# Wire_Puzzle.net
KiCad netlist of a schematic drawn in EAGLE
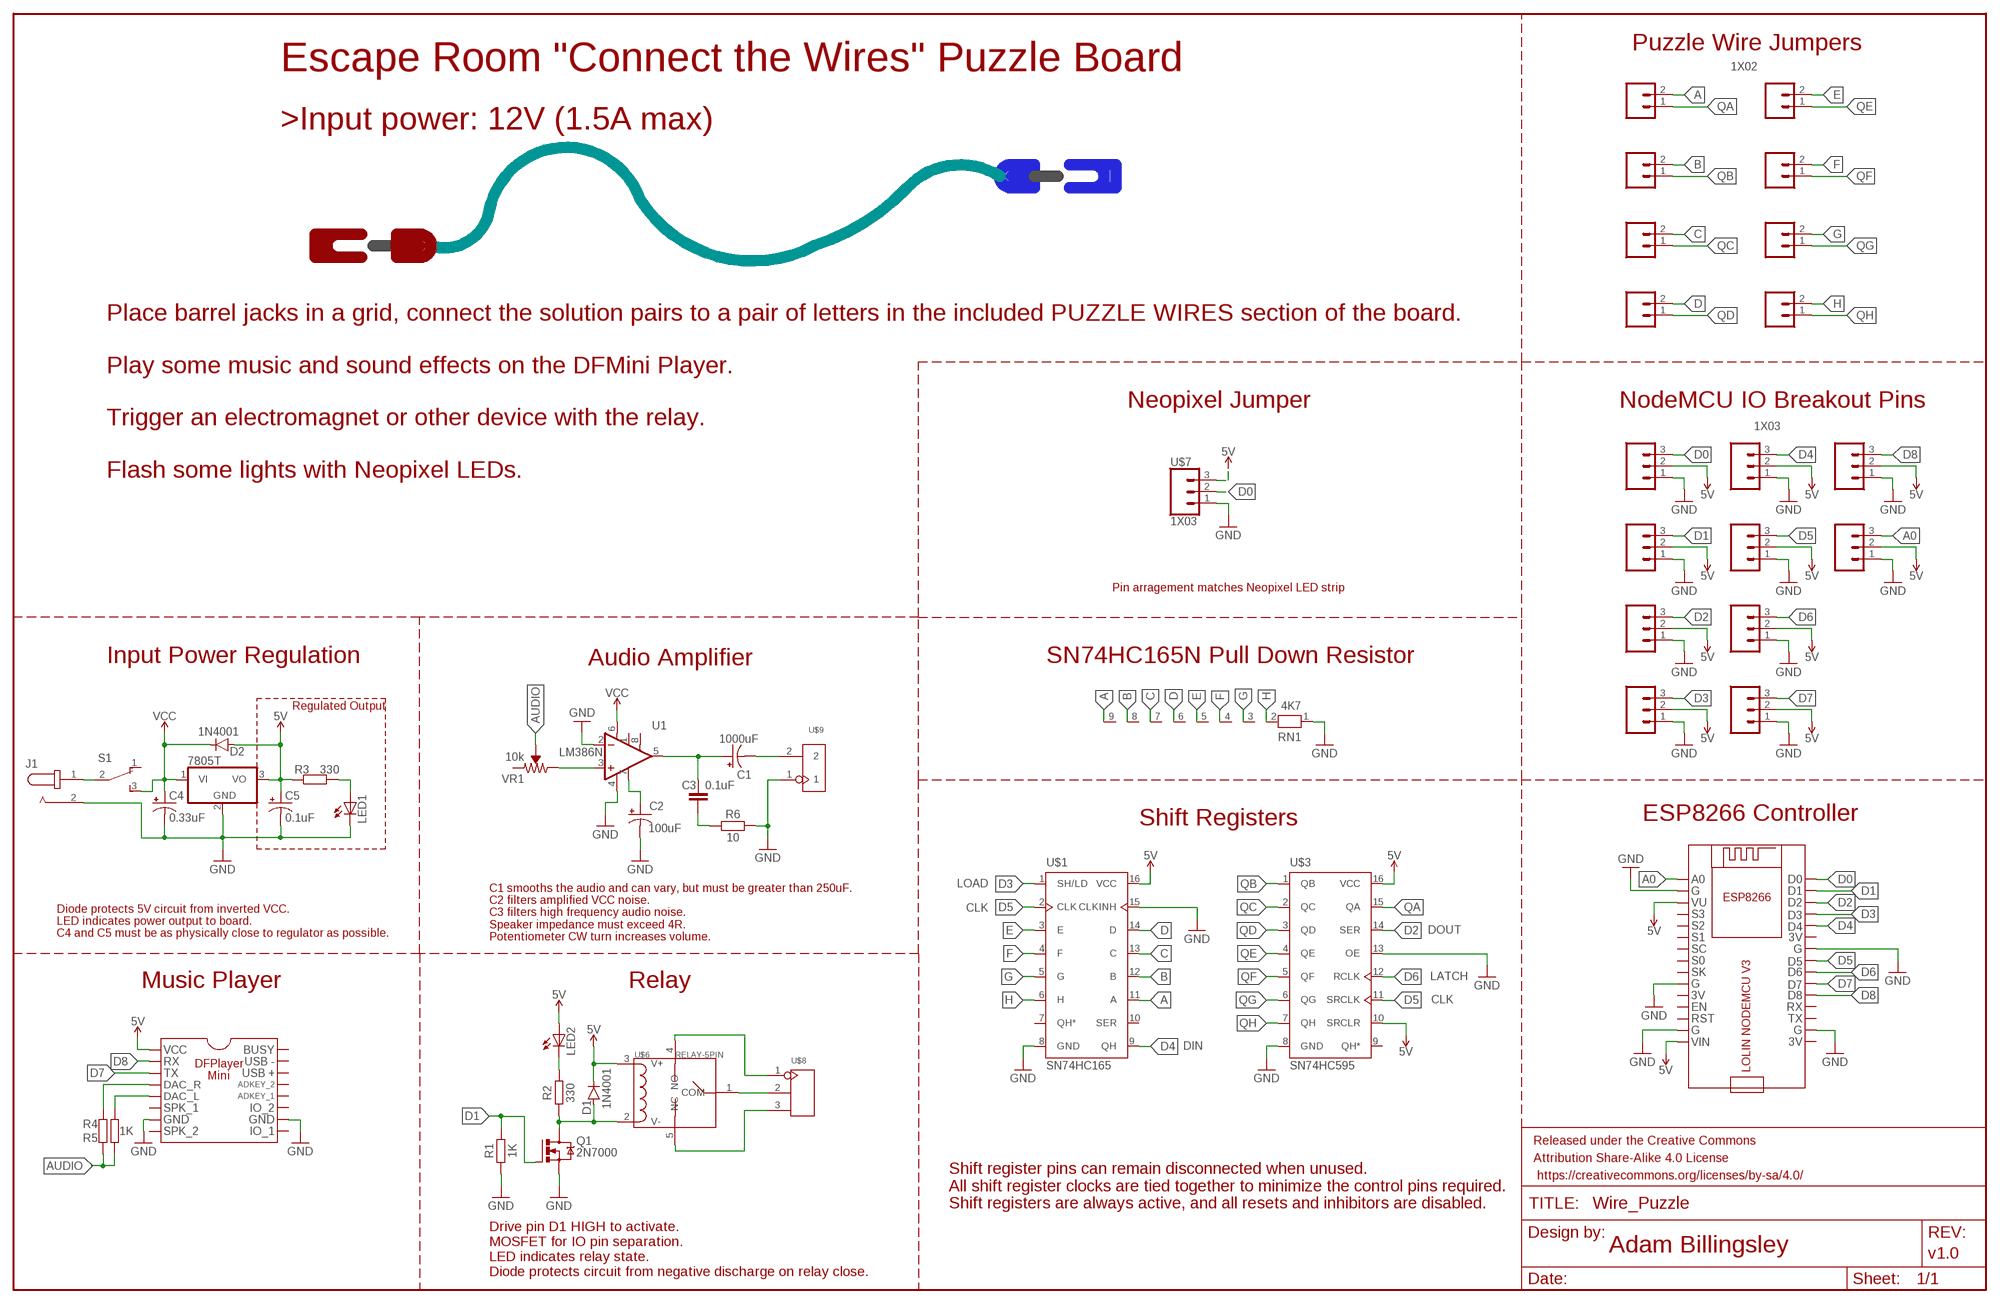
[diagram p0: schematic, sheet 1]

(export (version "E")
  (design (tool "Eeschema 10.0.6"))
  (components
    (comp (ref "C1")
      (value "1000uF")
      (footprint "eagle-import:E5-10,5")
      (libsource (lib "eagle-import") (part "CPOL-USE5-10.5"))
    )
    (comp (ref "C2")
      (value "100uF")
      (footprint "eagle-import:E5-10,5")
      (libsource (lib "eagle-import") (part "CPOL-USE5-10.5"))
    )
    (comp (ref "C3")
      (value "0.1uF")
      (footprint "eagle-import:C2.5-2")
      (libsource (lib "eagle-import") (part "C2.5/2"))
    )
    (comp (ref "C4")
      (value "0.33uF")
      (footprint "eagle-import:E2-5")
      (libsource (lib "eagle-import") (part "rcl_334_CPOL-USE2-5"))
    )
    (comp (ref "C5")
      (value "0.1uF")
      (footprint "eagle-import:E2-5")
      (libsource (lib "eagle-import") (part "rcl_334_CPOL-USE2-5"))
    )
    (comp (ref "D1")
      (value "1N4001")
      (footprint "eagle-import:DO-41")
      (fields
        (field (name "DIGIKEY_PART_NUMBER") "1N4004MSCT-ND")
        (field (name "MANUFACTURER") "Micro Commercial Co")
        (field (name "MPN") "1N4004")
        (field (name "CREATED_BY") "PCBLayout.com")
      )
      (libsource (lib "eagle-import") (part "1N4004"))
    )
    (comp (ref "D2")
      (value "1N4001")
      (footprint "eagle-import:DO-41")
      (fields
        (field (name "DIGIKEY_PART_NUMBER") "1N4004MSCT-ND")
        (field (name "MANUFACTURER") "Micro Commercial Co")
        (field (name "MPN") "1N4004")
        (field (name "CREATED_BY") "PCBLayout.com")
      )
      (libsource (lib "eagle-import") (part "1N4004"))
    )
    (comp (ref "FRAME1")
      (value "FRAME-LEDGER")
      (footprint "eagle-import:CREATIVE_COMMONS")
      (libsource (lib "eagle-import") (part "FRAME-LEDGER"))
    )
    (comp (ref "IC1")
      (value "7805T")
      (footprint "eagle-import:TO220H")
      (libsource (lib "eagle-import") (part "78T05"))
    )
    (comp (ref "J1")
      (value "POWER_JACK_PJ-037A")
      (footprint "eagle-import:CUI_PJ-037A")
      (fields (field (name "MANUFACTURER") "CUI INC"))
      (libsource (lib "eagle-import") (part "POWER_JACK_PJ-037A"))
    )
    (comp (ref "LED1")
      (value "LED5MM")
      (footprint "eagle-import:LED5MM")
      (libsource (lib "eagle-import") (part "LED5MM"))
    )
    (comp (ref "LED2")
      (value "LED5MM")
      (footprint "eagle-import:LED5MM")
      (libsource (lib "eagle-import") (part "LED5MM"))
    )
    (comp (ref "Q1")
      (value "2N7000")
      (footprint "eagle-import:TO92")
      (libsource (lib "eagle-import") (part "NMOSFET_TO92_"))
    )
    (comp (ref "R1")
      (value "1K")
      (footprint "eagle-import:RESAD724W46L381D178B")
      (libsource (lib "eagle-import") (part "RAXIAL-7.2MM-PITCH_"))
    )
    (comp (ref "R2")
      (value "330")
      (footprint "eagle-import:RESAD724W46L381D178B")
      (libsource (lib "eagle-import") (part "RAXIAL-7.2MM-PITCH_"))
    )
    (comp (ref "R3")
      (value "330")
      (footprint "eagle-import:RESAD724W46L381D178B")
      (libsource (lib "eagle-import") (part "RAXIAL-7.2MM-PITCH_"))
    )
    (comp (ref "R4")
      (value "1K")
      (footprint "eagle-import:RESAD724W46L381D178B")
      (libsource (lib "eagle-import") (part "RAXIAL-7.2MM-PITCH_"))
    )
    (comp (ref "R5")
      (value "1K")
      (footprint "eagle-import:RESAD724W46L381D178B")
      (libsource (lib "eagle-import") (part "RAXIAL-7.2MM-PITCH_"))
    )
    (comp (ref "R6")
      (value "10")
      (footprint "eagle-import:RESAD724W46L381D178B")
      (libsource (lib "eagle-import") (part "RAXIAL-7.2MM-PITCH_"))
    )
    (comp (ref "RN1")
      (value "4K7")
      (footprint "eagle-import:RN-9")
      (libsource (lib "eagle-import") (part "RN08"))
    )
    (comp (ref "S1")
      (value "SWITCH_SLIDING_SSP1S1")
      (footprint "eagle-import:SWITCH_SLIDING_SSP1S1")
      (libsource (lib "eagle-import") (part "SWITCH_SLIDING_SSP1S1"))
    )
    (comp (ref "U$1")
      (value "SN74HC165")
      (footprint "eagle-import:DIL16")
      (libsource (lib "eagle-import") (part "SN74HC165"))
    )
    (comp (ref "U$3")
      (value "SN74HC595")
      (footprint "eagle-import:DIL16")
      (libsource (lib "eagle-import") (part "SN74HC595"))
    )
    (comp (ref "U$4")
      (value "LOLIN_NODEMCU")
      (footprint "eagle-import:LOLIN_NODEMCU")
      (libsource (lib "eagle-import") (part "LOLIN_NODEMCU"))
    )
    (comp (ref "U$5")
      (value "DFPLAYER_MINI")
      (footprint "eagle-import:DFMINI")
      (libsource (lib "eagle-import") (part "DFPLAYER_MINI"))
    )
    (comp (ref "U$6")
      (value "RELAY-5PIN")
      (footprint "eagle-import:RELAY-19.0X15.0X15.0MM")
      (libsource (lib "eagle-import") (part "RELAY-5PIN"))
    )
    (comp (ref "U$7")
      (value "1X03")
      (footprint "eagle-import:1X03")
      (libsource (lib "eagle-import") (part "1X03"))
    )
    (comp (ref "U$8")
      (value "TERMINAL_BLOCK_3P")
      (footprint "eagle-import:H3-5.0-15.5X8.0MM")
      (libsource (lib "eagle-import") (part "TERMINAL_BLOCK_3P"))
    )
    (comp (ref "U$9")
      (value "TERMINAL_BLOCK_2P")
      (footprint "eagle-import:H2-5.0-10.5X8.0MM")
      (libsource (lib "eagle-import") (part "TERMINAL_BLOCK_2P"))
    )
    (comp (ref "U$10")
      (value "1X02")
      (footprint "eagle-import:1X02")
      (libsource (lib "eagle-import") (part "1X02"))
    )
    (comp (ref "U$11")
      (value "1X02")
      (footprint "eagle-import:1X02")
      (libsource (lib "eagle-import") (part "1X02"))
    )
    (comp (ref "U$12")
      (value "1X02")
      (footprint "eagle-import:1X02")
      (libsource (lib "eagle-import") (part "1X02"))
    )
    (comp (ref "U$13")
      (value "1X02")
      (footprint "eagle-import:1X02")
      (libsource (lib "eagle-import") (part "1X02"))
    )
    (comp (ref "U$14")
      (value "1X02")
      (footprint "eagle-import:1X02")
      (libsource (lib "eagle-import") (part "1X02"))
    )
    (comp (ref "U$15")
      (value "1X02")
      (footprint "eagle-import:1X02")
      (libsource (lib "eagle-import") (part "1X02"))
    )
    (comp (ref "U$16")
      (value "1X02")
      (footprint "eagle-import:1X02")
      (libsource (lib "eagle-import") (part "1X02"))
    )
    (comp (ref "U$17")
      (value "1X02")
      (footprint "eagle-import:1X02")
      (libsource (lib "eagle-import") (part "1X02"))
    )
    (comp (ref "U$18")
      (value "1X03")
      (footprint "eagle-import:1X03")
      (libsource (lib "eagle-import") (part "1X03"))
    )
    (comp (ref "U$19")
      (value "1X03")
      (footprint "eagle-import:1X03")
      (libsource (lib "eagle-import") (part "1X03"))
    )
    (comp (ref "U$20")
      (value "1X03")
      (footprint "eagle-import:1X03")
      (libsource (lib "eagle-import") (part "1X03"))
    )
    (comp (ref "U$21")
      (value "1X03")
      (footprint "eagle-import:1X03")
      (libsource (lib "eagle-import") (part "1X03"))
    )
    (comp (ref "U$22")
      (value "1X03")
      (footprint "eagle-import:1X03")
      (libsource (lib "eagle-import") (part "1X03"))
    )
    (comp (ref "U$23")
      (value "1X03")
      (footprint "eagle-import:1X03")
      (libsource (lib "eagle-import") (part "1X03"))
    )
    (comp (ref "U$24")
      (value "1X03")
      (footprint "eagle-import:1X03")
      (libsource (lib "eagle-import") (part "1X03"))
    )
    (comp (ref "U$25")
      (value "1X03")
      (footprint "eagle-import:1X03")
      (libsource (lib "eagle-import") (part "1X03"))
    )
    (comp (ref "U$26")
      (value "1X03")
      (footprint "eagle-import:1X03")
      (libsource (lib "eagle-import") (part "1X03"))
    )
    (comp (ref "U$27")
      (value "1X03")
      (footprint "eagle-import:1X03")
      (libsource (lib "eagle-import") (part "1X03"))
    )
    (comp (ref "U1")
      (value "LM386N")
      (footprint "eagle-import:DIP08")
      (libsource (lib "eagle-import") (part "LM386"))
    )
    (comp (ref "VR1")
      (value "10k")
      (footprint "eagle-import:TRIMPOT-PTH-3386U")
      (libsource (lib "eagle-import") (part "TRIMPOT-PTH-10MM-KNOB-1/2W-10%"))
    )
  )
  (nets
    (net (code "1") (name "/3V_1") (class "Default")
      (node (ref "U$4") (pin "P$5") (pinfunction "3V_1_P$5") (pintype "power_in"))
    )
    (net (code "2") (name "/3V_2") (class "Default")
      (node (ref "U$4") (pin "P$17") (pinfunction "3V_2_P$17") (pintype "power_in"))
    )
    (net (code "3") (name "/3V_3") (class "Default")
      (node (ref "U$4") (pin "P$26") (pinfunction "3V_3_P$26") (pintype "power_in"))
    )
    (net (code "4") (name "5V") (class "Default")
      (node (ref "C5") (pin "+") (pinfunction "+_+") (pintype "passive"))
      (node (ref "D1") (pin "C") (pinfunction "C_C") (pintype "passive"))
      (node (ref "D2") (pin "A") (pinfunction "A_A") (pintype "passive"))
      (node (ref "IC1") (pin "3") (pinfunction "VO_3") (pintype "passive"))
      (node (ref "LED2") (pin "A") (pinfunction "A_A") (pintype "passive"))
      (node (ref "R3") (pin "1") (pinfunction "1_1") (pintype "passive"))
      (node (ref "U$1") (pin "16") (pinfunction "VCC_16") (pintype "power_in"))
      (node (ref "U$18") (pin "2") (pinfunction "2_2") (pintype "passive"))
      (node (ref "U$19") (pin "2") (pinfunction "2_2") (pintype "passive"))
      (node (ref "U$20") (pin "2") (pinfunction "2_2") (pintype "passive"))
      (node (ref "U$21") (pin "2") (pinfunction "2_2") (pintype "passive"))
      (node (ref "U$22") (pin "2") (pinfunction "2_2") (pintype "passive"))
      (node (ref "U$23") (pin "2") (pinfunction "2_2") (pintype "passive"))
      (node (ref "U$24") (pin "2") (pinfunction "2_2") (pintype "passive"))
      (node (ref "U$25") (pin "2") (pinfunction "2_2") (pintype "passive"))
      (node (ref "U$26") (pin "2") (pinfunction "2_2") (pintype "passive"))
      (node (ref "U$27") (pin "2") (pinfunction "2_2") (pintype "passive"))
      (node (ref "U$3") (pin "10") (pinfunction "SRCLR_10") (pintype "open_collector"))
      (node (ref "U$3") (pin "16") (pinfunction "VCC_16") (pintype "power_in"))
      (node (ref "U$4") (pin "P$1") (pinfunction "VIN_P$1") (pintype "power_in"))
      (node (ref "U$4") (pin "P$13") (pinfunction "VU_P$13") (pintype "power_in"))
      (node (ref "U$5") (pin "P$9") (pinfunction "P$9_P$9") (pintype "power_in"))
      (node (ref "U$6") (pin "3") (pinfunction "V+_3") (pintype "bidirectional"))
      (node (ref "U$7") (pin "3") (pinfunction "3_3") (pintype "passive"))
    )
    (net (code "5") (name "A") (class "Default")
      (node (ref "RN1") (pin "9") (pinfunction "9_9") (pintype "passive"))
      (node (ref "U$1") (pin "11") (pinfunction "A_11") (pintype "input"))
      (node (ref "U$10") (pin "2") (pinfunction "2_2") (pintype "passive"))
    )
    (net (code "6") (name "A0") (class "Default")
      (node (ref "U$27") (pin "3") (pinfunction "3_3") (pintype "passive"))
      (node (ref "U$4") (pin "P$15") (pinfunction "A0_P$15") (pintype "bidirectional"))
    )
    (net (code "7") (name "AUDIO") (class "Default")
      (node (ref "R4") (pin "1") (pinfunction "1_1") (pintype "passive"))
      (node (ref "R5") (pin "1") (pinfunction "1_1") (pintype "passive"))
      (node (ref "VR1") (pin "2") (pinfunction "WIPER_2") (pintype "passive"))
    )
    (net (code "8") (name "B") (class "Default")
      (node (ref "RN1") (pin "8") (pinfunction "8_8") (pintype "passive"))
      (node (ref "U$1") (pin "12") (pinfunction "B_12") (pintype "input"))
      (node (ref "U$11") (pin "2") (pinfunction "2_2") (pintype "passive"))
    )
    (net (code "9") (name "C") (class "Default")
      (node (ref "RN1") (pin "7") (pinfunction "7_7") (pintype "passive"))
      (node (ref "U$1") (pin "13") (pinfunction "C_13") (pintype "input"))
      (node (ref "U$12") (pin "2") (pinfunction "2_2") (pintype "passive"))
    )
    (net (code "10") (name "D") (class "Default")
      (node (ref "RN1") (pin "6") (pinfunction "6_6") (pintype "passive"))
      (node (ref "U$1") (pin "14") (pinfunction "D_14") (pintype "input"))
      (node (ref "U$13") (pin "2") (pinfunction "2_2") (pintype "passive"))
    )
    (net (code "11") (name "D0") (class "Default")
      (node (ref "U$18") (pin "3") (pinfunction "3_3") (pintype "passive"))
      (node (ref "U$4") (pin "P$31") (pinfunction "D0_P$31") (pintype "bidirectional"))
      (node (ref "U$7") (pin "2") (pinfunction "2_2") (pintype "passive"))
    )
    (net (code "12") (name "D1") (class "Default")
      (node (ref "Q1") (pin "2") (pinfunction "G_2") (pintype "passive"))
      (node (ref "R1") (pin "1") (pinfunction "1_1") (pintype "passive"))
      (node (ref "U$19") (pin "3") (pinfunction "3_3") (pintype "passive"))
      (node (ref "U$4") (pin "P$30") (pinfunction "D1_P$30") (pintype "bidirectional"))
    )
    (net (code "13") (name "D2") (class "Default")
      (node (ref "U$20") (pin "3") (pinfunction "3_3") (pintype "passive"))
      (node (ref "U$3") (pin "14") (pinfunction "SER_14") (pintype "input"))
      (node (ref "U$4") (pin "P$29") (pinfunction "D2_P$29") (pintype "bidirectional"))
    )
    (net (code "14") (name "D3") (class "Default")
      (node (ref "U$1") (pin "1") (pinfunction "SH/LD_1") (pintype "open_collector"))
      (node (ref "U$21") (pin "3") (pinfunction "3_3") (pintype "passive"))
      (node (ref "U$4") (pin "P$28") (pinfunction "D3_P$28") (pintype "bidirectional"))
    )
    (net (code "15") (name "D4") (class "Default")
      (node (ref "U$1") (pin "9") (pinfunction "QH_9") (pintype "output"))
      (node (ref "U$22") (pin "3") (pinfunction "3_3") (pintype "passive"))
      (node (ref "U$4") (pin "P$27") (pinfunction "D4_P$27") (pintype "bidirectional"))
    )
    (net (code "16") (name "D5") (class "Default")
      (node (ref "U$1") (pin "2") (pinfunction "CLK_2") (pintype "input"))
      (node (ref "U$23") (pin "3") (pinfunction "3_3") (pintype "passive"))
      (node (ref "U$3") (pin "11") (pinfunction "SRCLK_11") (pintype "input"))
      (node (ref "U$4") (pin "P$24") (pinfunction "D5_P$24") (pintype "bidirectional"))
    )
    (net (code "17") (name "D6") (class "Default")
      (node (ref "U$24") (pin "3") (pinfunction "3_3") (pintype "passive"))
      (node (ref "U$3") (pin "12") (pinfunction "RCLK_12") (pintype "input"))
      (node (ref "U$4") (pin "P$23") (pinfunction "D6_P$23") (pintype "bidirectional"))
    )
    (net (code "18") (name "D7") (class "Default")
      (node (ref "U$25") (pin "3") (pinfunction "3_3") (pintype "passive"))
      (node (ref "U$4") (pin "P$22") (pinfunction "D7_P$22") (pintype "bidirectional"))
      (node (ref "U$5") (pin "P$11") (pinfunction "P$11_P$11") (pintype "bidirectional"))
    )
    (net (code "19") (name "D8") (class "Default")
      (node (ref "U$26") (pin "3") (pinfunction "3_3") (pintype "passive"))
      (node (ref "U$4") (pin "P$21") (pinfunction "D8_P$21") (pintype "bidirectional"))
      (node (ref "U$5") (pin "P$10") (pinfunction "P$10_P$10") (pintype "bidirectional"))
    )
    (net (code "20") (name "E") (class "Default")
      (node (ref "RN1") (pin "5") (pinfunction "5_5") (pintype "passive"))
      (node (ref "U$1") (pin "3") (pinfunction "E_3") (pintype "input"))
      (node (ref "U$14") (pin "2") (pinfunction "2_2") (pintype "passive"))
    )
    (net (code "21") (name "F") (class "Default")
      (node (ref "RN1") (pin "4") (pinfunction "4_4") (pintype "passive"))
      (node (ref "U$1") (pin "4") (pinfunction "F_4") (pintype "input"))
      (node (ref "U$15") (pin "2") (pinfunction "2_2") (pintype "passive"))
    )
    (net (code "22") (name "G") (class "Default")
      (node (ref "RN1") (pin "3") (pinfunction "3_3") (pintype "passive"))
      (node (ref "U$1") (pin "5") (pinfunction "G_5") (pintype "input"))
      (node (ref "U$16") (pin "2") (pinfunction "2_2") (pintype "passive"))
    )
    (net (code "23") (name "GND") (class "Default")
      (node (ref "C2") (pin "-") (pinfunction "-_-") (pintype "passive"))
      (node (ref "C4") (pin "-") (pinfunction "-_-") (pintype "passive"))
      (node (ref "C5") (pin "-") (pinfunction "-_-") (pintype "passive"))
      (node (ref "IC1") (pin "2") (pinfunction "GND_2") (pintype "passive"))
      (node (ref "J1") (pin "2") (pinfunction "2_2") (pintype "passive"))
      (node (ref "LED1") (pin "K") (pinfunction "C_K") (pintype "passive"))
      (node (ref "Q1") (pin "3") (pinfunction "S_3") (pintype "passive"))
      (node (ref "R1") (pin "2") (pinfunction "2_2") (pintype "passive"))
      (node (ref "R6") (pin "2") (pinfunction "2_2") (pintype "passive"))
      (node (ref "RN1") (pin "1") (pinfunction "1_1") (pintype "passive"))
      (node (ref "U$1") (pin "15") (pinfunction "CLKINH_15") (pintype "input"))
      (node (ref "U$1") (pin "8") (pinfunction "GND_8") (pintype "power_in"))
      (node (ref "U$18") (pin "1") (pinfunction "1_1") (pintype "passive"))
      (node (ref "U$19") (pin "1") (pinfunction "1_1") (pintype "passive"))
      (node (ref "U$20") (pin "1") (pinfunction "1_1") (pintype "passive"))
      (node (ref "U$21") (pin "1") (pinfunction "1_1") (pintype "passive"))
      (node (ref "U$22") (pin "1") (pinfunction "1_1") (pintype "passive"))
      (node (ref "U$23") (pin "1") (pinfunction "1_1") (pintype "passive"))
      (node (ref "U$24") (pin "1") (pinfunction "1_1") (pintype "passive"))
      (node (ref "U$25") (pin "1") (pinfunction "1_1") (pintype "passive"))
      (node (ref "U$26") (pin "1") (pinfunction "1_1") (pintype "passive"))
      (node (ref "U$27") (pin "1") (pinfunction "1_1") (pintype "passive"))
      (node (ref "U$3") (pin "13") (pinfunction "OE_13") (pintype "open_collector"))
      (node (ref "U$3") (pin "8") (pinfunction "GND_8") (pintype "power_in"))
      (node (ref "U$4") (pin "P$14") (pinfunction "G_3_P$14") (pintype "power_in"))
      (node (ref "U$4") (pin "P$18") (pinfunction "G_4_P$18") (pintype "power_in"))
      (node (ref "U$4") (pin "P$2") (pinfunction "G_1_P$2") (pintype "power_in"))
      (node (ref "U$4") (pin "P$25") (pinfunction "G_5_P$25") (pintype "power_in"))
      (node (ref "U$4") (pin "P$6") (pinfunction "G_2_P$6") (pintype "power_in"))
      (node (ref "U$5") (pin "P$15") (pinfunction "P$15_P$15") (pintype "power_in"))
      (node (ref "U$5") (pin "P$7") (pinfunction "P$7_P$7") (pintype "power_in"))
      (node (ref "U$7") (pin "1") (pinfunction "1_1") (pintype "passive"))
      (node (ref "U$9") (pin "1") (pinfunction "1_1") (pintype "bidirectional"))
      (node (ref "U1") (pin "2") (pinfunction "-IN_2") (pintype "input"))
      (node (ref "U1") (pin "4") (pinfunction "V-_4") (pintype "power_in"))
    )
    (net (code "24") (name "H") (class "Default")
      (node (ref "RN1") (pin "2") (pinfunction "2_2") (pintype "passive"))
      (node (ref "U$1") (pin "6") (pinfunction "H_6") (pintype "input"))
      (node (ref "U$17") (pin "2") (pinfunction "2_2") (pintype "passive"))
    )
    (net (code "25") (name "Net-(C1-Pad-)") (class "Default")
      (node (ref "C1") (pin "-") (pinfunction "-_-") (pintype "passive"))
      (node (ref "U$9") (pin "2") (pinfunction "2_2") (pintype "bidirectional"))
    )
    (net (code "26") (name "Net-(C3-Pad2)") (class "Default")
      (node (ref "C3") (pin "2") (pinfunction "2_2") (pintype "passive"))
      (node (ref "R6") (pin "1") (pinfunction "1_1") (pintype "passive"))
    )
    (net (code "27") (name "Net-(LED1-PadA)") (class "Default")
      (node (ref "LED1") (pin "A") (pinfunction "A_A") (pintype "passive"))
      (node (ref "R3") (pin "2") (pinfunction "2_2") (pintype "passive"))
    )
    (net (code "28") (name "Net-(LED2-C)") (class "Default")
      (node (ref "LED2") (pin "K") (pinfunction "C_K") (pintype "passive"))
      (node (ref "R2") (pin "2") (pinfunction "2_2") (pintype "passive"))
    )
    (net (code "29") (name "Net-(Q1-D)") (class "Default")
      (node (ref "D1") (pin "A") (pinfunction "A_A") (pintype "passive"))
      (node (ref "Q1") (pin "1") (pinfunction "D_1") (pintype "passive"))
      (node (ref "R2") (pin "1") (pinfunction "1_1") (pintype "passive"))
      (node (ref "U$6") (pin "2") (pinfunction "V-_2") (pintype "bidirectional"))
    )
    (net (code "30") (name "Net-(R4-Pad2)") (class "Default")
      (node (ref "R4") (pin "2") (pinfunction "2_2") (pintype "passive"))
      (node (ref "U$5") (pin "P$12") (pinfunction "P$12_P$12") (pintype "bidirectional"))
    )
    (net (code "31") (name "Net-(R5-Pad2)") (class "Default")
      (node (ref "R5") (pin "2") (pinfunction "2_2") (pintype "passive"))
      (node (ref "U$5") (pin "P$13") (pinfunction "P$13_P$13") (pintype "bidirectional"))
    )
    (net (code "32") (name "Net-(S1-P)") (class "Default")
      (node (ref "J1") (pin "1") (pinfunction "1_1") (pintype "passive"))
      (node (ref "S1") (pin "2") (pinfunction "P_2") (pintype "passive"))
    )
    (net (code "33") (name "Net-(U$6-COM)") (class "Default")
      (node (ref "U$6") (pin "1") (pinfunction "COM_1") (pintype "bidirectional"))
      (node (ref "U$8") (pin "2") (pinfunction "P$2_2") (pintype "bidirectional"))
    )
    (net (code "34") (name "Net-(U$6-NC)") (class "Default")
      (node (ref "U$6") (pin "5") (pinfunction "NC_5") (pintype "bidirectional"))
      (node (ref "U$8") (pin "3") (pinfunction "P$3_3") (pintype "bidirectional"))
    )
    (net (code "35") (name "Net-(U$6-NO)") (class "Default")
      (node (ref "U$6") (pin "4") (pinfunction "NO_4") (pintype "bidirectional"))
      (node (ref "U$8") (pin "1") (pinfunction "P$1_1") (pintype "bidirectional"))
    )
    (net (code "36") (name "Net-(U1-+IN)") (class "Default")
      (node (ref "U1") (pin "3") (pinfunction "+IN_3") (pintype "input"))
      (node (ref "VR1") (pin "3") (pinfunction "CW_3") (pintype "passive"))
    )
    (net (code "37") (name "Net-(U1-BP)") (class "Default")
      (node (ref "C2") (pin "+") (pinfunction "+_+") (pintype "passive"))
      (node (ref "U1") (pin "7") (pinfunction "BP_7") (pintype "bidirectional"))
    )
    (net (code "38") (name "Net-(U1-OUT)") (class "Default")
      (node (ref "C1") (pin "+") (pinfunction "+_+") (pintype "passive"))
      (node (ref "C3") (pin "1") (pinfunction "1_1") (pintype "passive"))
      (node (ref "U1") (pin "5") (pinfunction "OUT_5") (pintype "output"))
    )
    (net (code "39") (name "QA") (class "Default")
      (node (ref "U$10") (pin "1") (pinfunction "1_1") (pintype "passive"))
      (node (ref "U$3") (pin "15") (pinfunction "QA_15") (pintype "output"))
    )
    (net (code "40") (name "QB") (class "Default")
      (node (ref "U$11") (pin "1") (pinfunction "1_1") (pintype "passive"))
      (node (ref "U$3") (pin "1") (pinfunction "QB_1") (pintype "output"))
    )
    (net (code "41") (name "QC") (class "Default")
      (node (ref "U$12") (pin "1") (pinfunction "1_1") (pintype "passive"))
      (node (ref "U$3") (pin "2") (pinfunction "QC_2") (pintype "output"))
    )
    (net (code "42") (name "QD") (class "Default")
      (node (ref "U$13") (pin "1") (pinfunction "1_1") (pintype "passive"))
      (node (ref "U$3") (pin "3") (pinfunction "QD_3") (pintype "output"))
    )
    (net (code "43") (name "QE") (class "Default")
      (node (ref "U$14") (pin "1") (pinfunction "1_1") (pintype "passive"))
      (node (ref "U$3") (pin "4") (pinfunction "QE_4") (pintype "output"))
    )
    (net (code "44") (name "QF") (class "Default")
      (node (ref "U$15") (pin "1") (pinfunction "1_1") (pintype "passive"))
      (node (ref "U$3") (pin "5") (pinfunction "QF_5") (pintype "output"))
    )
    (net (code "45") (name "QG") (class "Default")
      (node (ref "U$16") (pin "1") (pinfunction "1_1") (pintype "passive"))
      (node (ref "U$3") (pin "6") (pinfunction "QG_6") (pintype "output"))
    )
    (net (code "46") (name "QH") (class "Default")
      (node (ref "U$17") (pin "1") (pinfunction "1_1") (pintype "passive"))
      (node (ref "U$3") (pin "7") (pinfunction "QH_7") (pintype "output"))
    )
    (net (code "47") (name "VCC") (class "Default")
      (node (ref "C4") (pin "+") (pinfunction "+_+") (pintype "passive"))
      (node (ref "D2") (pin "C") (pinfunction "C_C") (pintype "passive"))
      (node (ref "IC1") (pin "1") (pinfunction "VI_1") (pintype "input"))
      (node (ref "S1") (pin "3") (pinfunction "S_3") (pintype "passive"))
      (node (ref "U1") (pin "6") (pinfunction "V+_6") (pintype "power_in"))
    )
    (net (code "48") (name "unconnected-(S1-O-Pad1)") (class "Default")
      (node (ref "S1") (pin "1") (pinfunction "O_1") (pintype "passive"))
    )
    (net (code "49") (name "unconnected-(U$1-QH*-Pad7)") (class "Default")
      (node (ref "U$1") (pin "7") (pinfunction "QH*_7") (pintype "output"))
    )
    (net (code "50") (name "unconnected-(U$1-SER-Pad10)") (class "Default")
      (node (ref "U$1") (pin "10") (pinfunction "SER_10") (pintype "input"))
    )
    (net (code "51") (name "unconnected-(U$3-QH*-Pad9)") (class "Default")
      (node (ref "U$3") (pin "9") (pinfunction "QH*_9") (pintype "output"))
    )
    (net (code "52") (name "unconnected-(U$4-EN-PadP$4)") (class "Default")
      (node (ref "U$4") (pin "P$4") (pinfunction "EN_P$4") (pintype "input"))
    )
    (net (code "53") (name "unconnected-(U$4-RST-PadP$3)") (class "Default")
      (node (ref "U$4") (pin "P$3") (pinfunction "RST_P$3") (pintype "input"))
    )
    (net (code "54") (name "unconnected-(U$4-RX-PadP$20)") (class "Default")
      (node (ref "U$4") (pin "P$20") (pinfunction "RX_P$20") (pintype "input"))
    )
    (net (code "55") (name "unconnected-(U$4-S0-PadP$8)") (class "Default")
      (node (ref "U$4") (pin "P$8") (pinfunction "S0_P$8") (pintype "bidirectional"))
    )
    (net (code "56") (name "unconnected-(U$4-S1-PadP$10)") (class "Default")
      (node (ref "U$4") (pin "P$10") (pinfunction "S1_P$10") (pintype "bidirectional"))
    )
    (net (code "57") (name "unconnected-(U$4-S2-PadP$11)") (class "Default")
      (node (ref "U$4") (pin "P$11") (pinfunction "S2_P$11") (pintype "bidirectional"))
    )
    (net (code "58") (name "unconnected-(U$4-S3-PadP$12)") (class "Default")
      (node (ref "U$4") (pin "P$12") (pinfunction "S3_P$12") (pintype "bidirectional"))
    )
    (net (code "59") (name "unconnected-(U$4-SC-PadP$9)") (class "Default")
      (node (ref "U$4") (pin "P$9") (pinfunction "SC_P$9") (pintype "bidirectional"))
    )
    (net (code "60") (name "unconnected-(U$4-SK-PadP$7)") (class "Default")
      (node (ref "U$4") (pin "P$7") (pinfunction "SK_P$7") (pintype "bidirectional"))
    )
    (net (code "61") (name "unconnected-(U$4-TX-PadP$19)") (class "Default")
      (node (ref "U$4") (pin "P$19") (pinfunction "TX_P$19") (pintype "output"))
    )
    (net (code "62") (name "unconnected-(U$5-PadP$1)") (class "Default")
      (node (ref "U$5") (pin "P$1") (pinfunction "P$1_P$1") (pintype "bidirectional"))
    )
    (net (code "63") (name "unconnected-(U$5-PadP$2)") (class "Default")
      (node (ref "U$5") (pin "P$2") (pinfunction "P$2_P$2") (pintype "bidirectional"))
    )
    (net (code "64") (name "unconnected-(U$5-PadP$3)") (class "Default")
      (node (ref "U$5") (pin "P$3") (pinfunction "P$3_P$3") (pintype "bidirectional"))
    )
    (net (code "65") (name "unconnected-(U$5-PadP$4)") (class "Default")
      (node (ref "U$5") (pin "P$4") (pinfunction "P$4_P$4") (pintype "bidirectional"))
    )
    (net (code "66") (name "unconnected-(U$5-PadP$5)") (class "Default")
      (node (ref "U$5") (pin "P$5") (pinfunction "P$5_P$5") (pintype "bidirectional"))
    )
    (net (code "67") (name "unconnected-(U$5-PadP$6)") (class "Default")
      (node (ref "U$5") (pin "P$6") (pinfunction "P$6_P$6") (pintype "bidirectional"))
    )
    (net (code "68") (name "unconnected-(U$5-PadP$8)") (class "Default")
      (node (ref "U$5") (pin "P$8") (pinfunction "P$8_P$8") (pintype "bidirectional"))
    )
    (net (code "69") (name "unconnected-(U$5-PadP$14)") (class "Default")
      (node (ref "U$5") (pin "P$14") (pinfunction "P$14_P$14") (pintype "bidirectional"))
    )
    (net (code "70") (name "unconnected-(U$5-PadP$16)") (class "Default")
      (node (ref "U$5") (pin "P$16") (pinfunction "P$16_P$16") (pintype "bidirectional"))
    )
    (net (code "71") (name "unconnected-(U1-GAIN-Pad1)") (class "Default")
      (node (ref "U1") (pin "1") (pinfunction "GAIN_1") (pintype "bidirectional"))
    )
    (net (code "72") (name "unconnected-(U1-GAIN-Pad8)") (class "Default")
      (node (ref "U1") (pin "8") (pinfunction "GAIN_8") (pintype "bidirectional"))
    )
    (net (code "73") (name "unconnected-(VR1-CCW-Pad1)") (class "Default")
      (node (ref "VR1") (pin "1") (pinfunction "CCW_1") (pintype "passive"))
    )
  )
)
